# SchemaMicro.net
KiCad netlist of a schematic drawn in Altium Designer
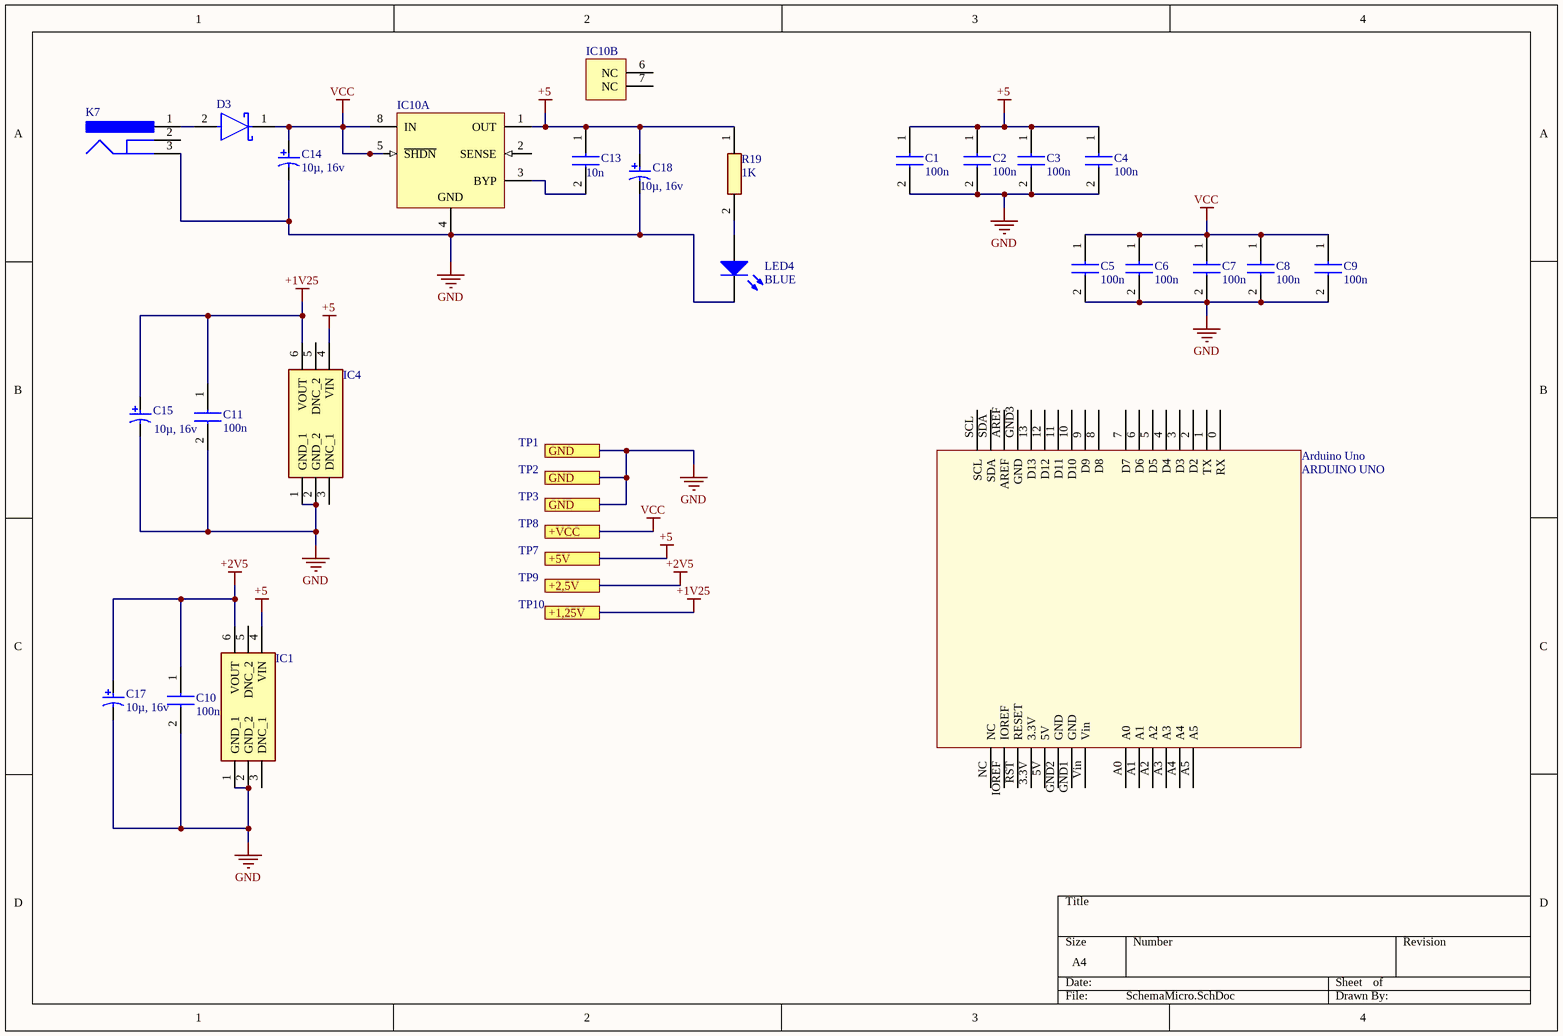
[diagram p0: SchemaMicro.SchDoc]

(export (version "E")
  (design (tool "Eeschema 10.0.6"))
  (components
    (comp (ref "Arduino Uno")
      (value "ARDUINO UNO")
      (footprint "ARDUINO UNO")
      (libsource (lib "Arduino") (part "ARDUINO UNO"))
    )
    (comp (ref "C1")
      (value "100n")
      (footprint "SamacSys:CAPC2012X90N")
      (description "Capacitor")
      (fields (field (name "MANUFACTURER_PART_NUMBER") "MC0805B104K500CT"))
      (libsource (lib "*") (part "MC0805B104K500CT"))
    )
    (comp (ref "C2")
      (value "100n")
      (footprint "SamacSys:CAPC2012X90N")
      (description "Capacitor")
      (fields (field (name "MANUFACTURER_PART_NUMBER") "MC0805B104K500CT"))
      (libsource (lib "*") (part "MC0805B104K500CT"))
    )
    (comp (ref "C3")
      (value "100n")
      (footprint "SamacSys:CAPC2012X90N")
      (description "Capacitor")
      (fields (field (name "MANUFACTURER_PART_NUMBER") "MC0805B104K500CT"))
      (libsource (lib "*") (part "MC0805B104K500CT"))
    )
    (comp (ref "C4")
      (value "100n")
      (footprint "SamacSys:CAPC2012X90N")
      (description "Capacitor")
      (fields (field (name "MANUFACTURER_PART_NUMBER") "MC0805B104K500CT"))
      (libsource (lib "*") (part "MC0805B104K500CT"))
    )
    (comp (ref "C5")
      (value "100n")
      (footprint "SamacSys:CAPC2012X90N")
      (description "Capacitor")
      (fields (field (name "MANUFACTURER_PART_NUMBER") "MC0805B104K500CT"))
      (libsource (lib "*") (part "MC0805B104K500CT"))
    )
    (comp (ref "C6")
      (value "100n")
      (footprint "SamacSys:CAPC2012X90N")
      (description "Capacitor")
      (fields (field (name "MANUFACTURER_PART_NUMBER") "MC0805B104K500CT"))
      (libsource (lib "*") (part "MC0805B104K500CT"))
    )
    (comp (ref "C7")
      (value "100n")
      (footprint "SamacSys:CAPC2012X90N")
      (description "Capacitor")
      (fields (field (name "MANUFACTURER_PART_NUMBER") "MC0805B104K500CT"))
      (libsource (lib "*") (part "MC0805B104K500CT"))
    )
    (comp (ref "C8")
      (value "100n")
      (footprint "SamacSys:CAPC2012X90N")
      (description "Capacitor")
      (fields (field (name "MANUFACTURER_PART_NUMBER") "MC0805B104K500CT"))
      (libsource (lib "*") (part "MC0805B104K500CT"))
    )
    (comp (ref "C9")
      (value "100n")
      (footprint "SamacSys:CAPC2012X90N")
      (description "Capacitor")
      (fields (field (name "MANUFACTURER_PART_NUMBER") "MC0805B104K500CT"))
      (libsource (lib "*") (part "MC0805B104K500CT"))
    )
    (comp (ref "C10")
      (value "100n")
      (footprint "SamacSys:CAPC2012X90N")
      (description "Capacitor")
      (fields (field (name "MANUFACTURER_PART_NUMBER") "MC0805B104K500CT"))
      (libsource (lib "*") (part "MC0805B104K500CT"))
    )
    (comp (ref "C11")
      (value "100n")
      (footprint "SamacSys:CAPC2012X90N")
      (description "Capacitor")
      (fields (field (name "MANUFACTURER_PART_NUMBER") "MC0805B104K500CT"))
      (libsource (lib "*") (part "MC0805B104K500CT"))
    )
    (comp (ref "C13")
      (value "10n")
      (footprint "SamacSys:CAPC2012X90N")
      (description "Capacitor")
      (fields (field (name "MANUFACTURER_PART_NUMBER") "MC0805N102J500CT"))
      (libsource (lib "*") (part "MC0805N102J500CT"))
    )
    (comp (ref "C14")
      (value "10µ, 16v")
      (footprint "KEMT-T491-B_L")
      (fields (field (name "MANUFACTURER") "Kemet") (field (name "VOLTAGE") "16VDC"))
      (libsource (lib "Altium Content Vault") (part "CAP-P-2"))
    )
    (comp (ref "C15")
      (value "10µ, 16v")
      (footprint "KEMT-T491-B_L")
      (fields (field (name "MANUFACTURER") "Kemet") (field (name "VOLTAGE") "16VDC"))
      (libsource (lib "Altium Content Vault") (part "CAP-P-2"))
    )
    (comp (ref "C17")
      (value "10µ, 16v")
      (footprint "KEMT-T491-B_L")
      (fields (field (name "MANUFACTURER") "Kemet") (field (name "VOLTAGE") "16VDC"))
      (libsource (lib "Altium Content Vault") (part "CAP-P-2"))
    )
    (comp (ref "C18")
      (value "10µ, 16v")
      (footprint "KEMT-T491-B_L")
      (fields (field (name "MANUFACTURER") "Kemet") (field (name "VOLTAGE") "16VDC"))
      (libsource (lib "Altium Content Vault") (part "CAP-P-2"))
    )
    (comp (ref "D3")
      (value "~")
      (footprint "FP-SOD123-IPC_A")
      (description "DIODE SCHOTTKY 40V 1A SOD123")
      (libsource (lib "Altium Content Vault") (part "1d6ec82d83fb6aee721767c19dac4b9"))
    )
    (comp (ref "IC1")
      (value "~")
      (footprint "SamacSys:SOT95P280X100-6N")
      (description "Integrated Circuit")
      (fields (field (name "MANUFACTURER_PART_NUMBER") "LT1790ACS6-2.048"))
      (libsource (lib "*") (part "LT1790ACS6-2.048"))
    )
    (comp (ref "IC4")
      (value "~")
      (footprint "SamacSys:LT1790BCS6125TRMPBF")
      (description "Integrated Circuit")
      (fields
        (field (name "MANUFACTURER_PART_NUMBER") "LT1790BCS6-1.25#TRMPBF")
        (field (name "MOUSER PART NUMBER") "584-1790BCS61.25TMPF")
      )
      (libsource (lib "SamacSys") (part "LT1790BCS6-1.25#TRMPBF"))
    )
    (comp (ref "IC10")
      (value "~")
      (footprint "LT-MS8_N")
      (fields
        (field (name "MANUFACTURER") "Linear Technology")
        (field (name "PARTNUMBER") "LT1762EMS8-5#PBF")
      )
      (libsource (lib "Altium Content Vault") (part "LT-LT1X62-MS8-8"))
    )
    (comp (ref "K7")
      (value "~")
      (footprint "LUMB-NEB21R_V")
      (description "Jack Socket, Body 14.5 x 9 mm, Height 11 mm, -20 to 70 degC, 3-Pin THD, RoHS, Bulk")
      (fields (field (name "MANUFACTURER") "Lumberg"))
      (libsource (lib "Altium Content Vault") (part "JACK-2CD3-RN"))
    )
    (comp (ref "LED4")
      (value "BLUE")
      (footprint "1206_A")
      (description "SMD mono-color Chip LED, WL-SMCW, Blue")
      (fields (field (name "MANUFACTURER") "Wuerth Elektronik") (field (name "PARTNUMBER") "150120BS75000"))
      (libsource (lib "Altium Content Vault") (part "WE-LED_K1A2-2"))
    )
    (comp (ref "R19")
      (value "1K")
      (footprint "SamacSys:RESC2014X65N")
      (description "Resistor 1K ohm")
      (fields (field (name "MANUFACTURER_PART_NUMBER") "MC01W080551K"))
      (libsource (lib "*") (part "MC01W080551K"))
    )
  )
  (nets
    (net (code "1") (name "+1V25") (class "Default")
      (node (ref "C11") (pin "1") (pinfunction "1_1") (pintype "passive"))
      (node (ref "C15") (pin "1") (pinfunction "1_1") (pintype "passive"))
      (node (ref "IC4") (pin "6") (pinfunction "VOUT_6") (pintype "passive"))
    )
    (net (code "2") (name "+2V5") (class "Default")
      (node (ref "C10") (pin "1") (pinfunction "1_1") (pintype "passive"))
      (node (ref "C17") (pin "1") (pinfunction "1_1") (pintype "passive"))
      (node (ref "IC1") (pin "6") (pinfunction "VOUT_6") (pintype "passive"))
    )
    (net (code "3") (name "+5") (class "Default")
      (node (ref "C1") (pin "1") (pinfunction "1_1") (pintype "passive"))
      (node (ref "C13") (pin "1") (pinfunction "1_1") (pintype "passive"))
      (node (ref "C18") (pin "1") (pinfunction "1_1") (pintype "passive"))
      (node (ref "C2") (pin "1") (pinfunction "1_1") (pintype "passive"))
      (node (ref "C3") (pin "1") (pinfunction "1_1") (pintype "passive"))
      (node (ref "C4") (pin "1") (pinfunction "1_1") (pintype "passive"))
      (node (ref "IC1") (pin "4") (pinfunction "VIN_4") (pintype "passive"))
      (node (ref "IC10") (pin "1") (pinfunction "OUT_1") (pintype "power_in"))
      (node (ref "IC4") (pin "4") (pinfunction "VIN_4") (pintype "passive"))
      (node (ref "R19") (pin "1") (pinfunction "1_1") (pintype "passive"))
    )
    (net (code "4") (name "GND") (class "Default")
      (node (ref "C1") (pin "2") (pinfunction "2_2") (pintype "passive"))
      (node (ref "C10") (pin "2") (pinfunction "2_2") (pintype "passive"))
      (node (ref "C11") (pin "2") (pinfunction "2_2") (pintype "passive"))
      (node (ref "C14") (pin "2") (pinfunction "2_2") (pintype "passive"))
      (node (ref "C15") (pin "2") (pinfunction "2_2") (pintype "passive"))
      (node (ref "C17") (pin "2") (pinfunction "2_2") (pintype "passive"))
      (node (ref "C18") (pin "2") (pinfunction "2_2") (pintype "passive"))
      (node (ref "C2") (pin "2") (pinfunction "2_2") (pintype "passive"))
      (node (ref "C3") (pin "2") (pinfunction "2_2") (pintype "passive"))
      (node (ref "C4") (pin "2") (pinfunction "2_2") (pintype "passive"))
      (node (ref "C5") (pin "2") (pinfunction "2_2") (pintype "passive"))
      (node (ref "C6") (pin "2") (pinfunction "2_2") (pintype "passive"))
      (node (ref "C7") (pin "2") (pinfunction "2_2") (pintype "passive"))
      (node (ref "C8") (pin "2") (pinfunction "2_2") (pintype "passive"))
      (node (ref "C9") (pin "2") (pinfunction "2_2") (pintype "passive"))
      (node (ref "IC1") (pin "1") (pinfunction "GND_1_1") (pintype "passive"))
      (node (ref "IC1") (pin "2") (pinfunction "GND_2_2") (pintype "passive"))
      (node (ref "IC10") (pin "4") (pinfunction "GND_4") (pintype "power_in"))
      (node (ref "IC4") (pin "1") (pinfunction "GND_1_1") (pintype "passive"))
      (node (ref "IC4") (pin "2") (pinfunction "GND_2_2") (pintype "passive"))
      (node (ref "K7") (pin "3") (pinfunction "3_3") (pintype "passive"))
      (node (ref "LED4") (pin "1") (pinfunction "K_1") (pintype "passive"))
    )
    (net (code "5") (name "Net-(D3-A)") (class "Default")
      (node (ref "D3") (pin "2") (pinfunction "A_2") (pintype "passive"))
      (node (ref "K7") (pin "1") (pinfunction "1_1") (pintype "passive"))
    )
    (net (code "6") (name "Net-(IC10A-BYP)") (class "Default")
      (node (ref "C13") (pin "2") (pinfunction "2_2") (pintype "passive"))
      (node (ref "IC10") (pin "3") (pinfunction "BYP_3") (pintype "passive"))
    )
    (net (code "7") (name "Net-(LED4-A)") (class "Default")
      (node (ref "LED4") (pin "2") (pinfunction "A_2") (pintype "passive"))
      (node (ref "R19") (pin "2") (pinfunction "2_2") (pintype "passive"))
    )
    (net (code "8") (name "VCC") (class "Default")
      (node (ref "C14") (pin "1") (pinfunction "1_1") (pintype "passive"))
      (node (ref "C5") (pin "1") (pinfunction "1_1") (pintype "passive"))
      (node (ref "C6") (pin "1") (pinfunction "1_1") (pintype "passive"))
      (node (ref "C7") (pin "1") (pinfunction "1_1") (pintype "passive"))
      (node (ref "C8") (pin "1") (pinfunction "1_1") (pintype "passive"))
      (node (ref "C9") (pin "1") (pinfunction "1_1") (pintype "passive"))
      (node (ref "D3") (pin "1") (pinfunction "C_1") (pintype "passive"))
      (node (ref "IC10") (pin "5") (pinfunction "~{SHDN}_5") (pintype "input"))
      (node (ref "IC10") (pin "8") (pinfunction "IN_8") (pintype "power_in"))
    )
    (net (code "9") (name "unconnected-(Arduino Uno-D2-Pad2)") (class "Default")
      (node (ref "Arduino Uno") (pin "2") (pinfunction "D2_2") (pintype "passive"))
    )
    (net (code "10") (name "unconnected-(Arduino Uno-D3-Pad3)") (class "Default")
      (node (ref "Arduino Uno") (pin "3") (pinfunction "D3_3") (pintype "passive"))
    )
    (net (code "11") (name "unconnected-(Arduino Uno-D4-Pad4)") (class "Default")
      (node (ref "Arduino Uno") (pin "4") (pinfunction "D4_4") (pintype "passive"))
    )
    (net (code "12") (name "unconnected-(Arduino Uno-D5-Pad5)") (class "Default")
      (node (ref "Arduino Uno") (pin "5") (pinfunction "D5_5") (pintype "passive"))
    )
    (net (code "13") (name "unconnected-(Arduino Uno-D6-Pad6)") (class "Default")
      (node (ref "Arduino Uno") (pin "6") (pinfunction "D6_6") (pintype "passive"))
    )
    (net (code "14") (name "unconnected-(Arduino Uno-D7-Pad7)") (class "Default")
      (node (ref "Arduino Uno") (pin "7") (pinfunction "D7_7") (pintype "passive"))
    )
    (net (code "15") (name "unconnected-(Arduino Uno-D8-Pad8)") (class "Default")
      (node (ref "Arduino Uno") (pin "8") (pinfunction "D8_8") (pintype "passive"))
    )
    (net (code "16") (name "unconnected-(Arduino Uno-D9-Pad9)") (class "Default")
      (node (ref "Arduino Uno") (pin "9") (pinfunction "D9_9") (pintype "passive"))
    )
    (net (code "17") (name "unconnected-(Arduino Uno-D10-Pad10)") (class "Default")
      (node (ref "Arduino Uno") (pin "10") (pinfunction "D10_10") (pintype "passive"))
    )
    (net (code "18") (name "unconnected-(Arduino Uno-D11-Pad11)") (class "Default")
      (node (ref "Arduino Uno") (pin "11") (pinfunction "D11_11") (pintype "passive"))
    )
    (net (code "19") (name "unconnected-(Arduino Uno-D12-Pad12)") (class "Default")
      (node (ref "Arduino Uno") (pin "12") (pinfunction "D12_12") (pintype "passive"))
    )
    (net (code "20") (name "unconnected-(Arduino Uno-D13-Pad13)") (class "Default")
      (node (ref "Arduino Uno") (pin "13") (pinfunction "D13_13") (pintype "passive"))
    )
    (net (code "21") (name "unconnected-(Arduino Uno-GND-PadGND1)") (class "Default")
      (node (ref "Arduino Uno") (pin "GND1") (pinfunction "GND_GND1") (pintype "passive"))
    )
    (net (code "22") (name "unconnected-(Arduino Uno-GND-PadGND2)") (class "Default")
      (node (ref "Arduino Uno") (pin "GND2") (pinfunction "GND_GND2") (pintype "passive"))
    )
    (net (code "23") (name "unconnected-(Arduino Uno-GND-PadGND3)") (class "Default")
      (node (ref "Arduino Uno") (pin "GND3") (pinfunction "GND_GND3") (pintype "passive"))
    )
    (net (code "24") (name "unconnected-(Arduino Uno-Pad3.3V)") (class "Default")
      (node (ref "Arduino Uno") (pin "3.3V") (pinfunction "3.3V_3.3V") (pintype "passive"))
    )
    (net (code "25") (name "unconnected-(Arduino Uno-Pad5V)") (class "Default")
      (node (ref "Arduino Uno") (pin "5V") (pinfunction "5V_5V") (pintype "passive"))
    )
    (net (code "26") (name "unconnected-(Arduino Uno-PadA0)") (class "Default")
      (node (ref "Arduino Uno") (pin "A0") (pinfunction "A0_A0") (pintype "passive"))
    )
    (net (code "27") (name "unconnected-(Arduino Uno-PadA1)") (class "Default")
      (node (ref "Arduino Uno") (pin "A1") (pinfunction "A1_A1") (pintype "passive"))
    )
    (net (code "28") (name "unconnected-(Arduino Uno-PadA2)") (class "Default")
      (node (ref "Arduino Uno") (pin "A2") (pinfunction "A2_A2") (pintype "passive"))
    )
    (net (code "29") (name "unconnected-(Arduino Uno-PadA3)") (class "Default")
      (node (ref "Arduino Uno") (pin "A3") (pinfunction "A3_A3") (pintype "passive"))
    )
    (net (code "30") (name "unconnected-(Arduino Uno-PadA4)") (class "Default")
      (node (ref "Arduino Uno") (pin "A4") (pinfunction "A4_A4") (pintype "passive"))
    )
    (net (code "31") (name "unconnected-(Arduino Uno-PadA5)") (class "Default")
      (node (ref "Arduino Uno") (pin "A5") (pinfunction "A5_A5") (pintype "passive"))
    )
    (net (code "32") (name "unconnected-(Arduino Uno-PadAREF)") (class "Default")
      (node (ref "Arduino Uno") (pin "AREF") (pinfunction "AREF_AREF") (pintype "passive"))
    )
    (net (code "33") (name "unconnected-(Arduino Uno-PadIOREF)") (class "Default")
      (node (ref "Arduino Uno") (pin "IOREF") (pinfunction "IOREF_IOREF") (pintype "passive"))
    )
    (net (code "34") (name "unconnected-(Arduino Uno-PadNC)") (class "Default")
      (node (ref "Arduino Uno") (pin "NC") (pinfunction "NC_NC") (pintype "passive"))
    )
    (net (code "35") (name "unconnected-(Arduino Uno-PadSCL)") (class "Default")
      (node (ref "Arduino Uno") (pin "SCL") (pinfunction "SCL_SCL") (pintype "passive"))
    )
    (net (code "36") (name "unconnected-(Arduino Uno-PadSDA)") (class "Default")
      (node (ref "Arduino Uno") (pin "SDA") (pinfunction "SDA_SDA") (pintype "passive"))
    )
    (net (code "37") (name "unconnected-(Arduino Uno-PadVin)") (class "Default")
      (node (ref "Arduino Uno") (pin "Vin") (pinfunction "Vin_Vin") (pintype "passive"))
    )
    (net (code "38") (name "unconnected-(Arduino Uno-RESET-PadRST)") (class "Default")
      (node (ref "Arduino Uno") (pin "RST") (pinfunction "RESET_RST") (pintype "passive"))
    )
    (net (code "39") (name "unconnected-(Arduino Uno-RX-Pad0)") (class "Default")
      (node (ref "Arduino Uno") (pin "0") (pinfunction "RX_0") (pintype "passive"))
    )
    (net (code "40") (name "unconnected-(Arduino Uno-TX-Pad1)") (class "Default")
      (node (ref "Arduino Uno") (pin "1") (pinfunction "TX_1") (pintype "passive"))
    )
    (net (code "41") (name "unconnected-(IC1-DNC_1-Pad3)") (class "Default")
      (node (ref "IC1") (pin "3") (pinfunction "DNC_1_3") (pintype "passive"))
    )
    (net (code "42") (name "unconnected-(IC1-DNC_2-Pad5)") (class "Default")
      (node (ref "IC1") (pin "5") (pinfunction "DNC_2_5") (pintype "passive"))
    )
    (net (code "43") (name "unconnected-(IC4-DNC_1-Pad3)") (class "Default")
      (node (ref "IC4") (pin "3") (pinfunction "DNC_1_3") (pintype "passive"))
    )
    (net (code "44") (name "unconnected-(IC4-DNC_2-Pad5)") (class "Default")
      (node (ref "IC4") (pin "5") (pinfunction "DNC_2_5") (pintype "passive"))
    )
    (net (code "45") (name "unconnected-(IC10A-SENSE-Pad2)") (class "Default")
      (node (ref "IC10") (pin "2") (pinfunction "SENSE_2") (pintype "input"))
    )
    (net (code "46") (name "unconnected-(IC10B-NC-Pad6)") (class "Default")
      (node (ref "IC10") (pin "6") (pinfunction "NC_6") (pintype "passive"))
    )
    (net (code "47") (name "unconnected-(IC10B-NC-Pad7)") (class "Default")
      (node (ref "IC10") (pin "7") (pinfunction "NC_7") (pintype "passive"))
    )
    (net (code "48") (name "unconnected-(K7-Pad2)") (class "Default")
      (node (ref "K7") (pin "2") (pinfunction "2_2") (pintype "passive"))
    )
  )
)
